# mixer.net
KiCad netlist of a schematic drawn in EAGLE
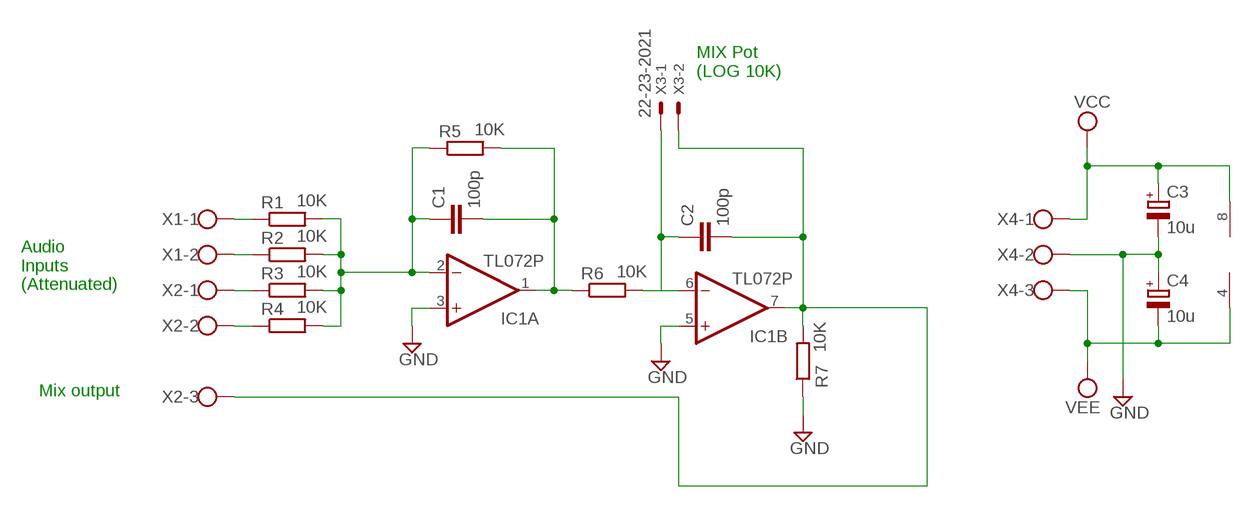
[diagram p0: schematic, sheet 1]

(export (version "E")
  (design (tool "Eeschema 10.0.6"))
  (components
    (comp (ref "C1")
      (value "100p")
      (footprint "eagle-import:C025-024X044")
      (libsource (lib "eagle-import") (part "C-EU025-024X044"))
    )
    (comp (ref "C2")
      (value "100p")
      (footprint "eagle-import:C025-024X044")
      (libsource (lib "eagle-import") (part "C-EU025-024X044"))
    )
    (comp (ref "C3")
      (value "10u")
      (footprint "eagle-import:E1,8-4")
      (libsource (lib "eagle-import") (part "CPOL-EUE1.8-4"))
    )
    (comp (ref "C4")
      (value "10u")
      (footprint "eagle-import:E1,8-4")
      (libsource (lib "eagle-import") (part "CPOL-EUE1.8-4"))
    )
    (comp (ref "IC1")
      (value "TL072P")
      (footprint "eagle-import:DIL08")
      (libsource (lib "eagle-import") (part "TL072P"))
    )
    (comp (ref "R1")
      (value "10K")
      (footprint "eagle-import:0204_7")
      (libsource (lib "eagle-import") (part "R-EU_0204/7"))
    )
    (comp (ref "R2")
      (value "10K")
      (footprint "eagle-import:0204_7")
      (libsource (lib "eagle-import") (part "R-EU_0204/7"))
    )
    (comp (ref "R3")
      (value "10K")
      (footprint "eagle-import:0204_7")
      (libsource (lib "eagle-import") (part "R-EU_0204/7"))
    )
    (comp (ref "R4")
      (value "10K")
      (footprint "eagle-import:0204_7")
      (libsource (lib "eagle-import") (part "R-EU_0204/7"))
    )
    (comp (ref "R5")
      (value "10K")
      (footprint "eagle-import:0204_7")
      (libsource (lib "eagle-import") (part "R-EU_0204/7"))
    )
    (comp (ref "R6")
      (value "10K")
      (footprint "eagle-import:0204_7")
      (libsource (lib "eagle-import") (part "R-EU_0204/7"))
    )
    (comp (ref "R7")
      (value "10K")
      (footprint "eagle-import:0204_7")
      (libsource (lib "eagle-import") (part "R-EU_0204/7"))
    )
    (comp (ref "X1")
      (value "W237-102")
      (footprint "eagle-import:W237-102")
      (fields (field (name "MPN") "237-102"))
      (libsource (lib "eagle-import") (part "W237-102"))
    )
    (comp (ref "X2")
      (value "W237-103")
      (footprint "eagle-import:W237-103")
      (fields (field (name "MPN") "237-103"))
      (libsource (lib "eagle-import") (part "W237-103"))
    )
    (comp (ref "X3")
      (value "22-23-2021")
      (footprint "eagle-import:22-23-2021")
      (fields (field (name "MF") "MOLEX"))
      (libsource (lib "eagle-import") (part "22-23-2021"))
    )
    (comp (ref "X4")
      (value "W237-103")
      (footprint "eagle-import:W237-103")
      (fields (field (name "MPN") "237-103"))
      (libsource (lib "eagle-import") (part "W237-103"))
    )
  )
  (nets
    (net (code "1") (name "GND") (class "Default")
      (node (ref "C3") (pin "-") (pinfunction "-_-") (pintype "passive"))
      (node (ref "C4") (pin "+") (pinfunction "+_+") (pintype "passive"))
      (node (ref "IC1") (pin "3") (pinfunction "+IN_3") (pintype "input"))
      (node (ref "IC1") (pin "5") (pinfunction "+IN_5") (pintype "input"))
      (node (ref "R7") (pin "1") (pinfunction "1_1") (pintype "passive"))
      (node (ref "X4") (pin "2") (pinfunction "KL_2") (pintype "passive"))
    )
    (net (code "2") (name "Net-(IC1A--IN)") (class "Default")
      (node (ref "C1") (pin "1") (pinfunction "1_1") (pintype "passive"))
      (node (ref "IC1") (pin "2") (pinfunction "-IN_2") (pintype "input"))
      (node (ref "R1") (pin "2") (pinfunction "2_2") (pintype "passive"))
      (node (ref "R2") (pin "2") (pinfunction "2_2") (pintype "passive"))
      (node (ref "R3") (pin "2") (pinfunction "2_2") (pintype "passive"))
      (node (ref "R4") (pin "2") (pinfunction "2_2") (pintype "passive"))
      (node (ref "R5") (pin "1") (pinfunction "1_1") (pintype "passive"))
    )
    (net (code "3") (name "Net-(IC1A-OUT)") (class "Default")
      (node (ref "C1") (pin "2") (pinfunction "2_2") (pintype "passive"))
      (node (ref "IC1") (pin "1") (pinfunction "OUT_1") (pintype "output"))
      (node (ref "R5") (pin "2") (pinfunction "2_2") (pintype "passive"))
      (node (ref "R6") (pin "1") (pinfunction "1_1") (pintype "passive"))
    )
    (net (code "4") (name "Net-(IC1B--IN)") (class "Default")
      (node (ref "C2") (pin "1") (pinfunction "1_1") (pintype "passive"))
      (node (ref "IC1") (pin "6") (pinfunction "-IN_6") (pintype "input"))
      (node (ref "R6") (pin "2") (pinfunction "2_2") (pintype "passive"))
      (node (ref "X3") (pin "1") (pinfunction "S_1") (pintype "passive"))
    )
    (net (code "5") (name "Net-(IC1B-OUT)") (class "Default")
      (node (ref "C2") (pin "2") (pinfunction "2_2") (pintype "passive"))
      (node (ref "IC1") (pin "7") (pinfunction "OUT_7") (pintype "output"))
      (node (ref "R7") (pin "2") (pinfunction "2_2") (pintype "passive"))
      (node (ref "X2") (pin "3") (pinfunction "KL_3") (pintype "passive"))
      (node (ref "X3") (pin "2") (pinfunction "S_2") (pintype "passive"))
    )
    (net (code "6") (name "Net-(X1A-KL)") (class "Default")
      (node (ref "R1") (pin "1") (pinfunction "1_1") (pintype "passive"))
      (node (ref "X1") (pin "1") (pinfunction "KL_1") (pintype "passive"))
    )
    (net (code "7") (name "Net-(X1B-KL)") (class "Default")
      (node (ref "R2") (pin "1") (pinfunction "1_1") (pintype "passive"))
      (node (ref "X1") (pin "2") (pinfunction "KL_2") (pintype "passive"))
    )
    (net (code "8") (name "Net-(X2A-KL)") (class "Default")
      (node (ref "R3") (pin "1") (pinfunction "1_1") (pintype "passive"))
      (node (ref "X2") (pin "1") (pinfunction "KL_1") (pintype "passive"))
    )
    (net (code "9") (name "Net-(X2B-KL)") (class "Default")
      (node (ref "R4") (pin "1") (pinfunction "1_1") (pintype "passive"))
      (node (ref "X2") (pin "2") (pinfunction "KL_2") (pintype "passive"))
    )
    (net (code "10") (name "VCC") (class "Default")
      (node (ref "C3") (pin "+") (pinfunction "+_+") (pintype "passive"))
      (node (ref "IC1") (pin "8") (pinfunction "V+_8") (pintype "power_in"))
      (node (ref "X4") (pin "1") (pinfunction "KL_1") (pintype "passive"))
    )
    (net (code "11") (name "VEE") (class "Default")
      (node (ref "C4") (pin "-") (pinfunction "-_-") (pintype "passive"))
      (node (ref "IC1") (pin "4") (pinfunction "V-_4") (pintype "power_in"))
      (node (ref "X4") (pin "3") (pinfunction "KL_3") (pintype "passive"))
    )
  )
)
